# S06-PERIPHERALS.net
KiCad netlist of a schematic drawn in Altium Designer
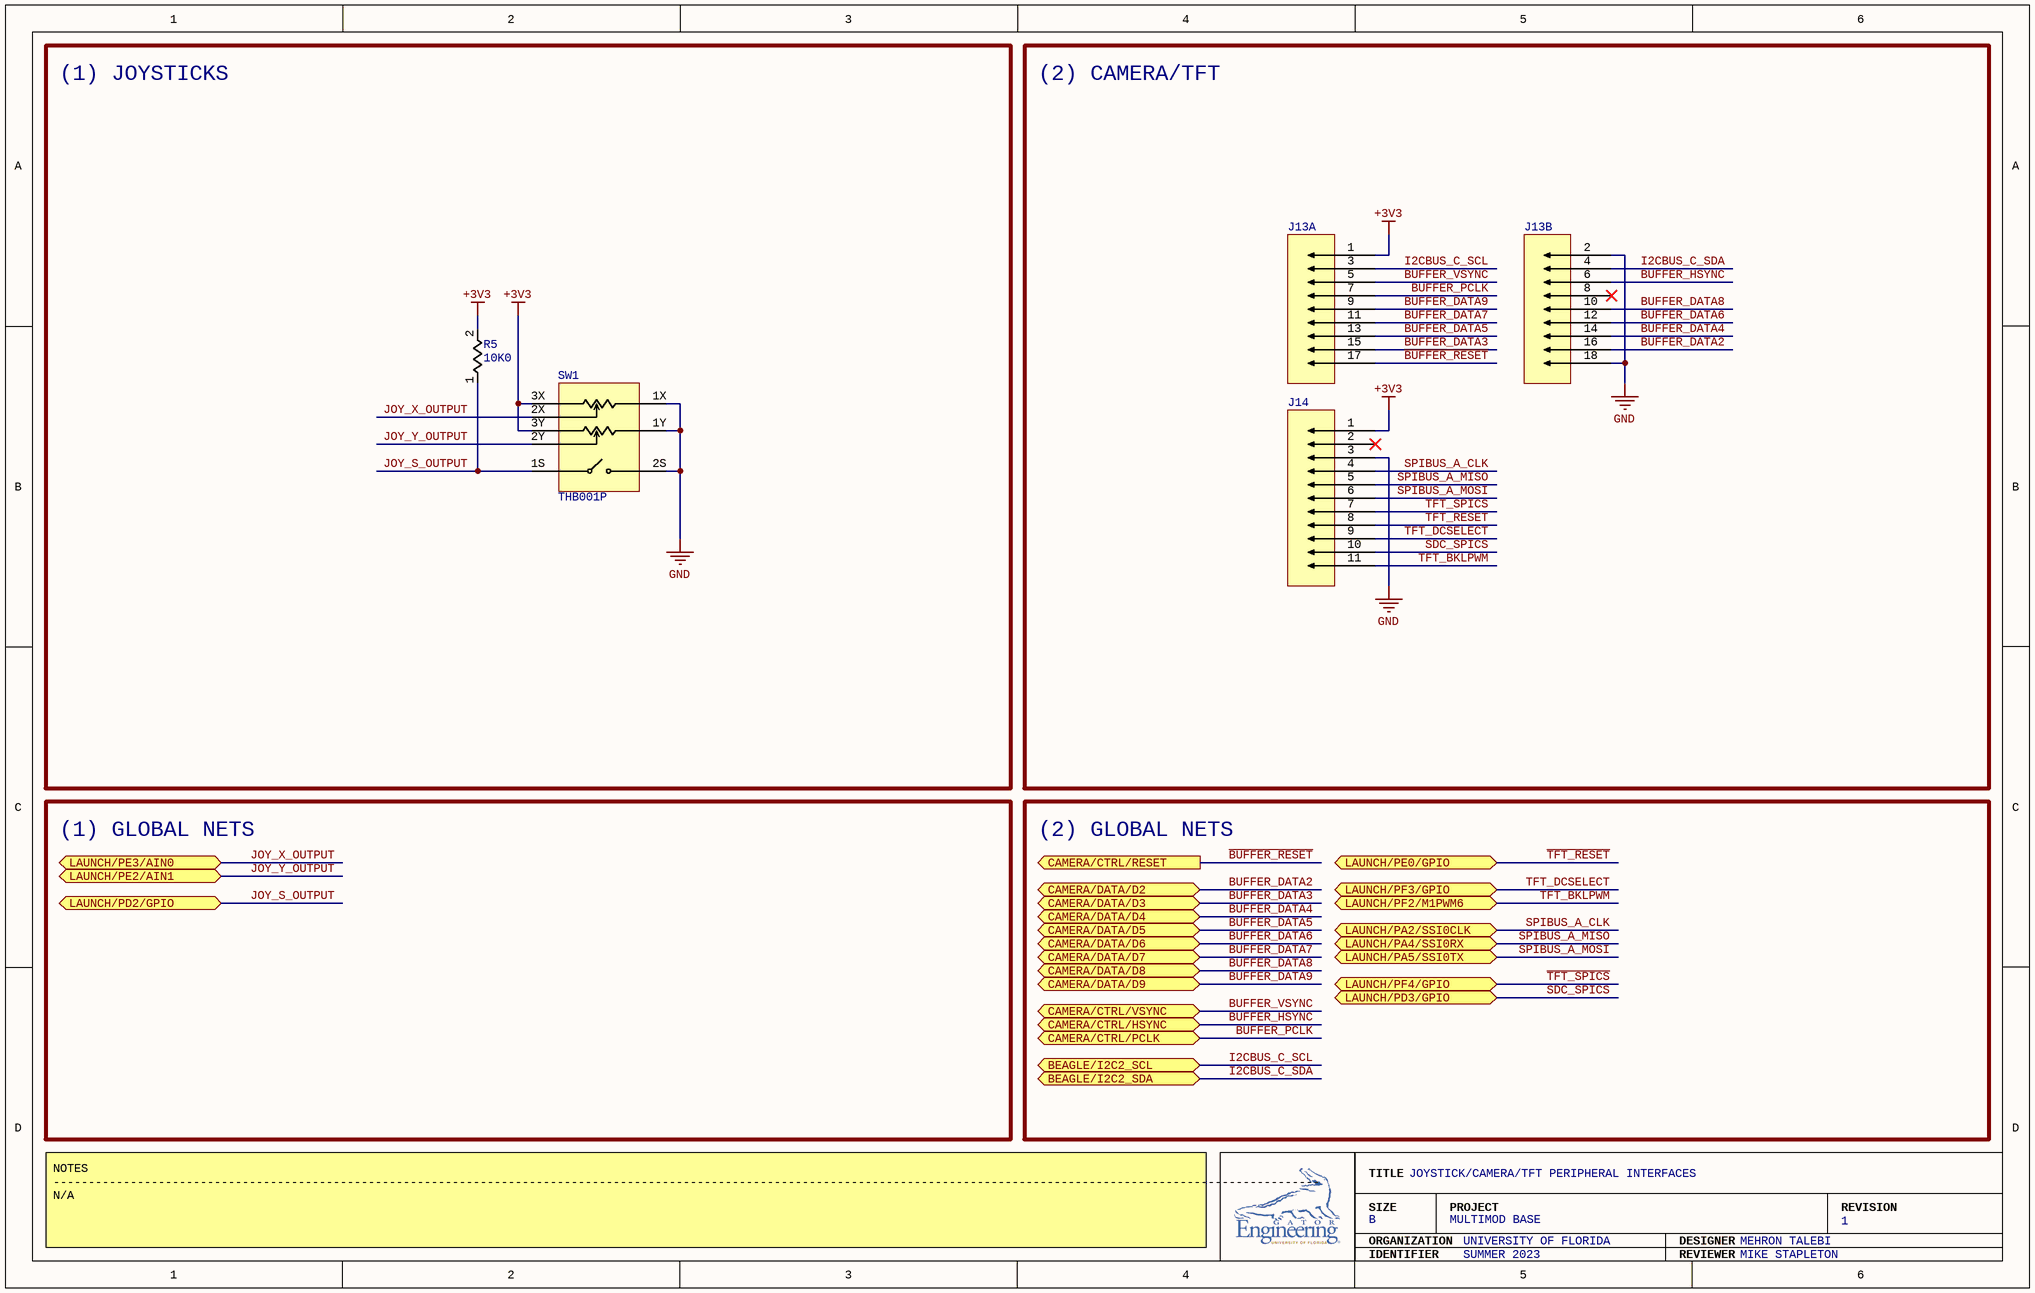
[diagram p0: S06-PERIPHERALS.SchDoc]

(export (version "E")
  (design (tool "Eeschema 10.0.6"))
  (components
    (comp (ref "J13")
      (value "PPPC092LJBN-RC")
      (footprint "PPPC092LJBN-RC")
      (description "CONN HDR 18POS 0.1 GOLD PCB R/A")
      (libsource (lib "Master") (part "PPPC092LJBN-RC"))
    )
    (comp (ref "J14")
      (value "PPPC111LFBN-RC")
      (footprint "PPPC111LFBN-RC")
      (description "CONN HDR 11POS 0.1 GOLD PCB")
      (libsource (lib "Master") (part "PPPC111LFBN-RC"))
    )
    (comp (ref "R5")
      (value "10K0")
      (footprint "RC0805FR-0710KL")
      (description "RES 10K OHM 1% 1/8W 0805")
      (fields (field (name "TOLERANCE") "±1%"))
      (libsource (lib "Master") (part "RC0805FR-0710KL"))
    )
    (comp (ref "SW1")
      (value "THB001P")
      (footprint "THB001P")
      (description "THUMBSTICK DUAL AXIS W/MOM PB")
      (libsource (lib "Master") (part "THB001P"))
    )
  )
  (nets
    (net (code "1") (name "+3V3") (class "Default")
      (node (ref "J13") (pin "1") (pinfunction "1_1") (pintype "passive"))
      (node (ref "J14") (pin "1") (pinfunction "1_1") (pintype "passive"))
      (node (ref "R5") (pin "2") (pinfunction "2_2") (pintype "passive"))
      (node (ref "SW1") (pin "3X") (pinfunction "3X_3X") (pintype "passive"))
      (node (ref "SW1") (pin "3Y") (pinfunction "3Y_3Y") (pintype "passive"))
    )
    (net (code "2") (name "/BUFFER_DATA2") (class "Default")
      (node (ref "J13") (pin "16") (pinfunction "16_16") (pintype "passive"))
    )
    (net (code "3") (name "/BUFFER_DATA3") (class "Default")
      (node (ref "J13") (pin "15") (pinfunction "15_15") (pintype "passive"))
    )
    (net (code "4") (name "/BUFFER_DATA4") (class "Default")
      (node (ref "J13") (pin "14") (pinfunction "14_14") (pintype "passive"))
    )
    (net (code "5") (name "/BUFFER_DATA5") (class "Default")
      (node (ref "J13") (pin "13") (pinfunction "13_13") (pintype "passive"))
    )
    (net (code "6") (name "/BUFFER_DATA6") (class "Default")
      (node (ref "J13") (pin "12") (pinfunction "12_12") (pintype "passive"))
    )
    (net (code "7") (name "/BUFFER_DATA7") (class "Default")
      (node (ref "J13") (pin "11") (pinfunction "11_11") (pintype "passive"))
    )
    (net (code "8") (name "/BUFFER_DATA8") (class "Default")
      (node (ref "J13") (pin "10") (pinfunction "10_10") (pintype "passive"))
    )
    (net (code "9") (name "/BUFFER_DATA9") (class "Default")
      (node (ref "J13") (pin "9") (pinfunction "9_9") (pintype "passive"))
    )
    (net (code "10") (name "/BUFFER_HSYNC") (class "Default")
      (node (ref "J13") (pin "6") (pinfunction "6_6") (pintype "passive"))
    )
    (net (code "11") (name "/BUFFER_PCLK") (class "Default")
      (node (ref "J13") (pin "7") (pinfunction "7_7") (pintype "passive"))
    )
    (net (code "12") (name "/BUFFER_RESET") (class "Default")
      (node (ref "J13") (pin "17") (pinfunction "17_17") (pintype "passive"))
    )
    (net (code "13") (name "/BUFFER_VSYNC") (class "Default")
      (node (ref "J13") (pin "5") (pinfunction "5_5") (pintype "passive"))
    )
    (net (code "14") (name "/I2CBUS_C_SCL") (class "Default")
      (node (ref "J13") (pin "3") (pinfunction "3_3") (pintype "passive"))
    )
    (net (code "15") (name "/I2CBUS_C_SDA") (class "Default")
      (node (ref "J13") (pin "4") (pinfunction "4_4") (pintype "passive"))
    )
    (net (code "16") (name "/JOY_S_OUTPUT") (class "Default")
      (node (ref "R5") (pin "1") (pinfunction "1_1") (pintype "passive"))
      (node (ref "SW1") (pin "1S") (pinfunction "1S_1S") (pintype "passive"))
    )
    (net (code "17") (name "/JOY_X_OUTPUT") (class "Default")
      (node (ref "SW1") (pin "2X") (pinfunction "2X_2X") (pintype "passive"))
    )
    (net (code "18") (name "/JOY_Y_OUTPUT") (class "Default")
      (node (ref "SW1") (pin "2Y") (pinfunction "2Y_2Y") (pintype "passive"))
    )
    (net (code "19") (name "/SDC_SPICS") (class "Default")
      (node (ref "J14") (pin "10") (pinfunction "10_10") (pintype "passive"))
    )
    (net (code "20") (name "/SPIBUS_A_CLK") (class "Default")
      (node (ref "J14") (pin "4") (pinfunction "4_4") (pintype "passive"))
    )
    (net (code "21") (name "/SPIBUS_A_MISO") (class "Default")
      (node (ref "J14") (pin "5") (pinfunction "5_5") (pintype "passive"))
    )
    (net (code "22") (name "/SPIBUS_A_MOSI") (class "Default")
      (node (ref "J14") (pin "6") (pinfunction "6_6") (pintype "passive"))
    )
    (net (code "23") (name "/TFT_BKLPWM") (class "Default")
      (node (ref "J14") (pin "11") (pinfunction "11_11") (pintype "passive"))
    )
    (net (code "24") (name "/TFT_DCSELECT") (class "Default")
      (node (ref "J14") (pin "9") (pinfunction "9_9") (pintype "passive"))
    )
    (net (code "25") (name "/TFT_RESET") (class "Default")
      (node (ref "J14") (pin "8") (pinfunction "8_8") (pintype "passive"))
    )
    (net (code "26") (name "/TFT_SPICS") (class "Default")
      (node (ref "J14") (pin "7") (pinfunction "7_7") (pintype "passive"))
    )
    (net (code "27") (name "GND") (class "Default")
      (node (ref "J13") (pin "18") (pinfunction "18_18") (pintype "passive"))
      (node (ref "J13") (pin "2") (pinfunction "2_2") (pintype "passive"))
      (node (ref "J14") (pin "3") (pinfunction "3_3") (pintype "passive"))
      (node (ref "SW1") (pin "1X") (pinfunction "1X_1X") (pintype "passive"))
      (node (ref "SW1") (pin "1Y") (pinfunction "1Y_1Y") (pintype "passive"))
      (node (ref "SW1") (pin "2S") (pinfunction "2S_2S") (pintype "passive"))
    )
    (net (code "28") (name "unconnected-(J13-Pad8)") (class "Default")
      (node (ref "J13") (pin "8") (pinfunction "8_8") (pintype "passive+no_connect"))
    )
    (net (code "29") (name "unconnected-(J14-Pad2)") (class "Default")
      (node (ref "J14") (pin "2") (pinfunction "2_2") (pintype "passive+no_connect"))
    )
  )
)
